# SCH_pie-day-pcb.net
KiCad netlist of a schematic drawn in EasyEDA
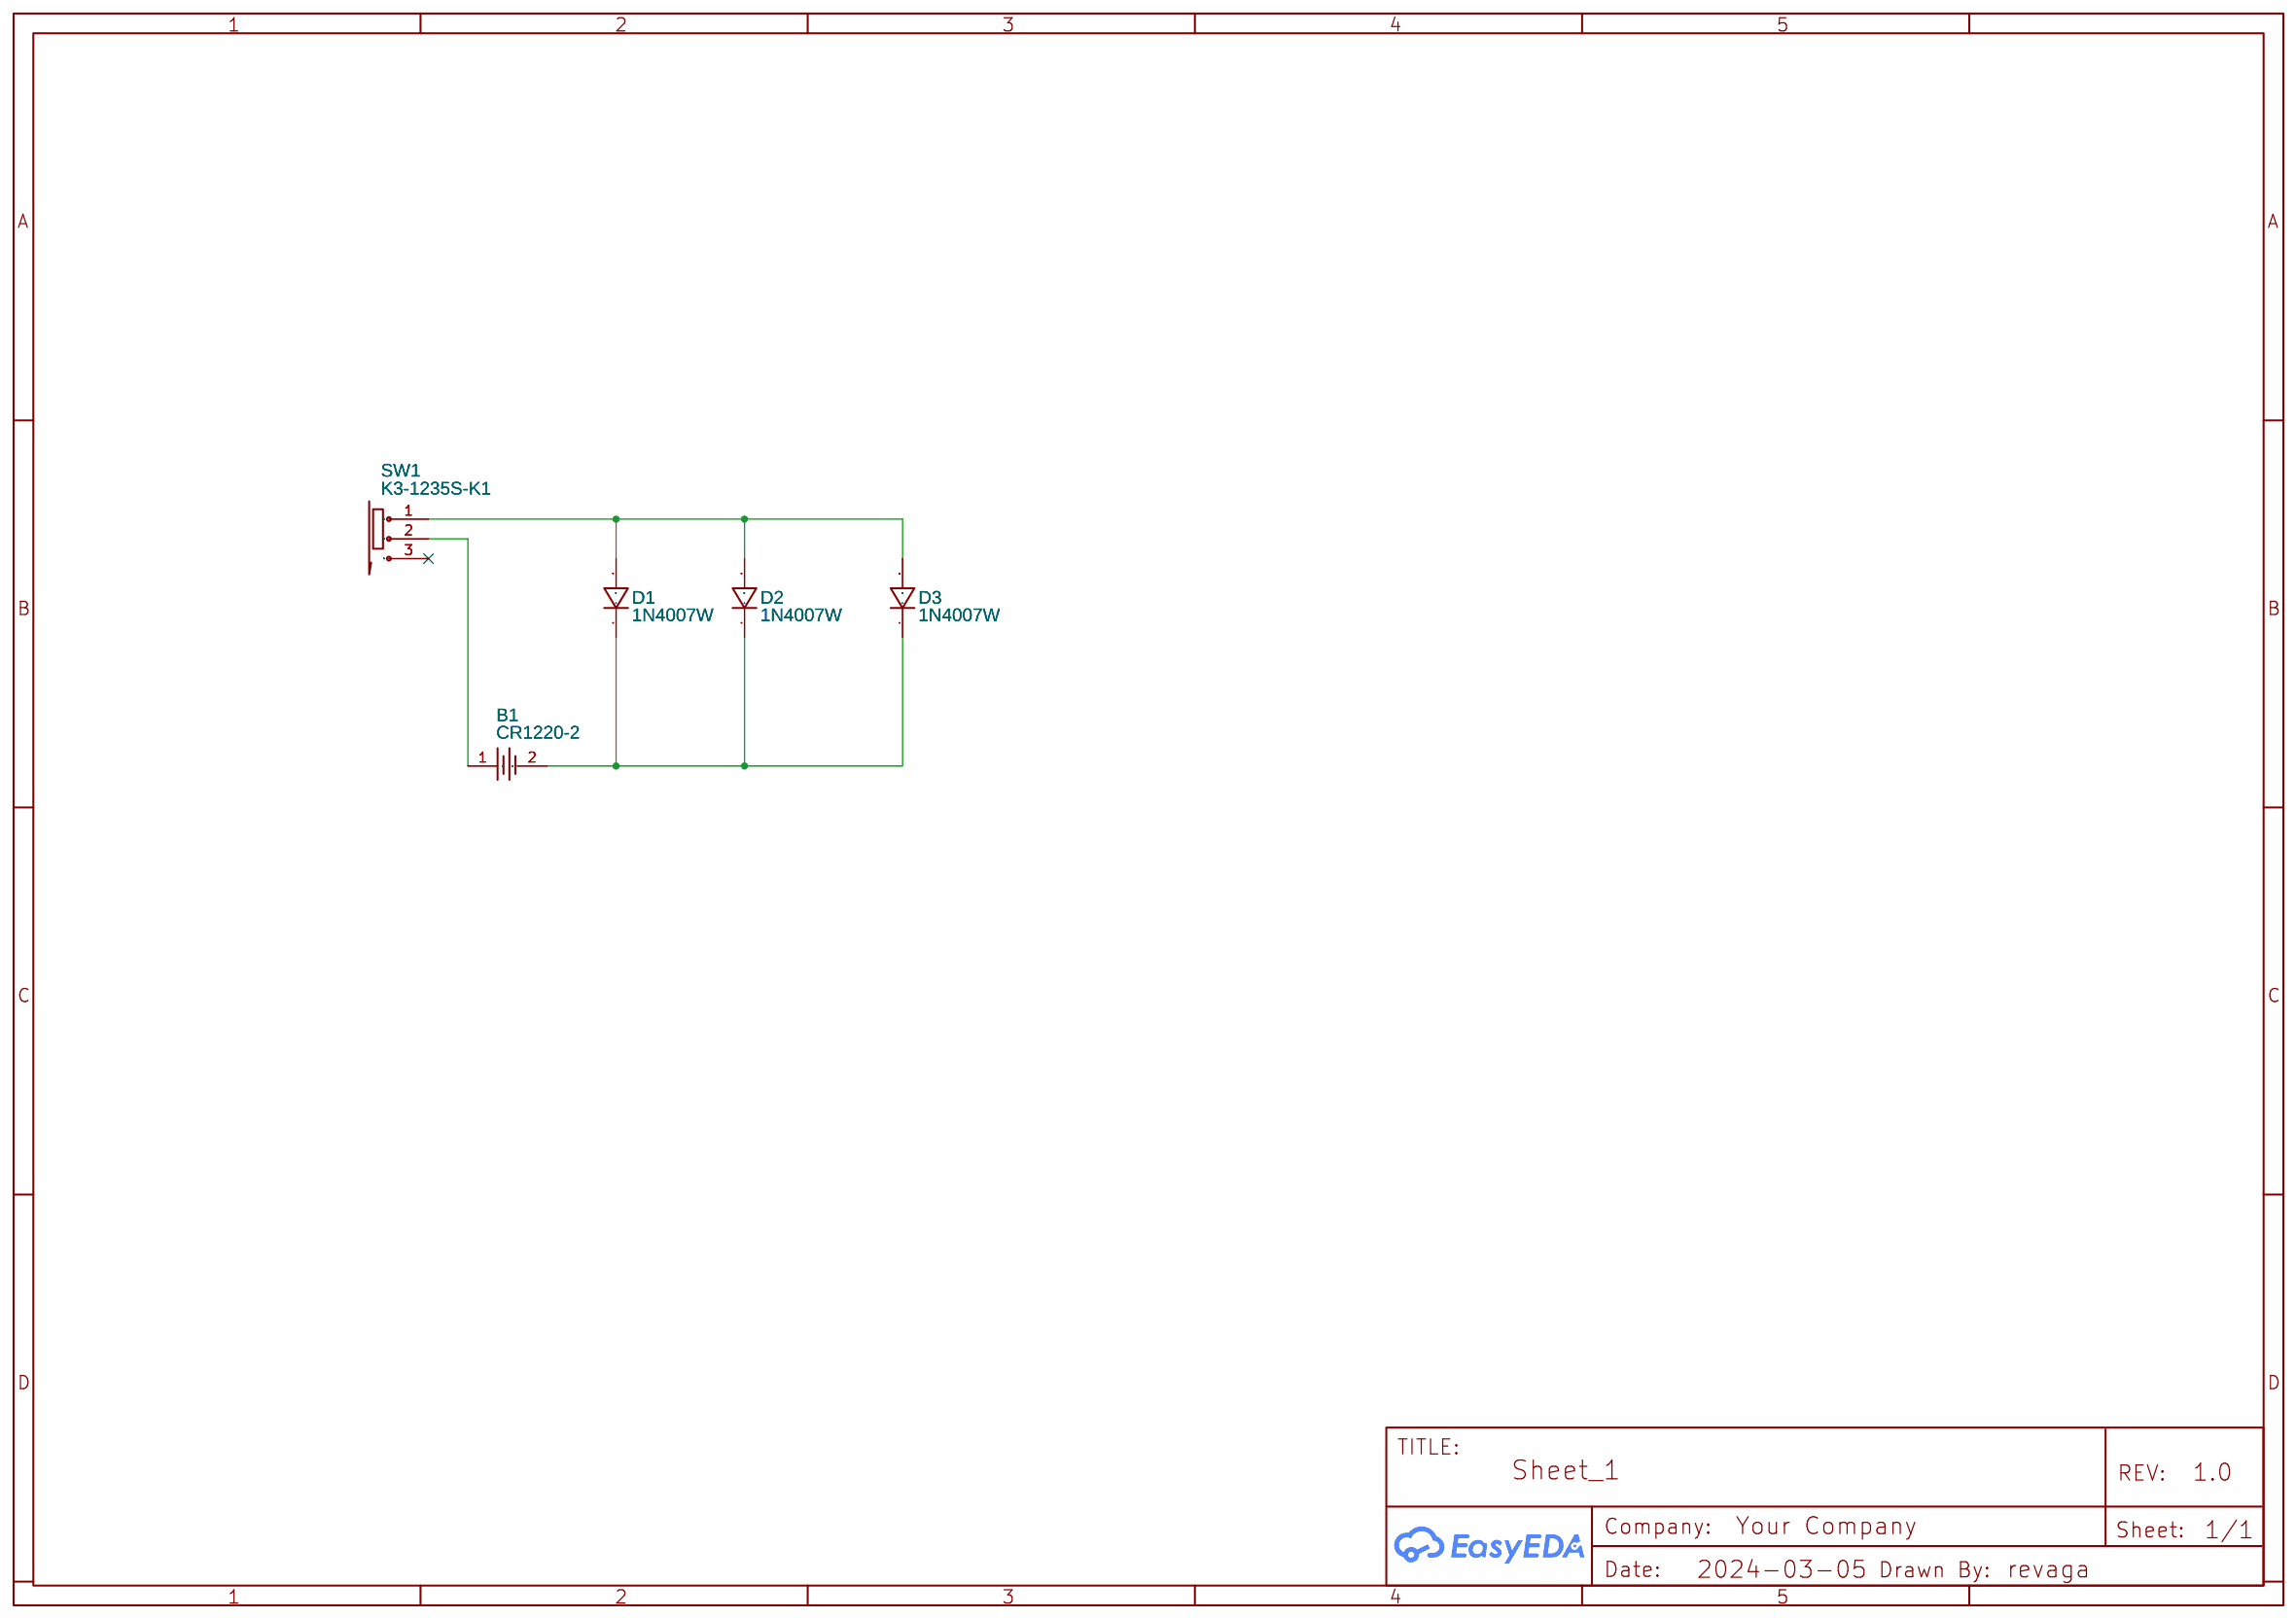
[diagram p0: schematic sheet]

(export (version "E")
  (design (tool "Eeschema 10.0.6"))
  (components
    (comp (ref "B1")
      (value "CR1220-2")
      (fields (field (name "Manufacturer") "Q&J"))
      (libsource (lib "") (part "CR1220-2"))
    )
    (comp (ref "D1")
      (value "1N4007W")
      (fields (field (name "Manufacturer") "BLUE ROCKET"))
      (libsource (lib "") (part "1N4007W"))
    )
    (comp (ref "D2")
      (value "1N4007W")
      (fields (field (name "Manufacturer") "BLUE ROCKET"))
      (libsource (lib "") (part "1N4007W"))
    )
    (comp (ref "D3")
      (value "1N4007W")
      (fields (field (name "Manufacturer") "BLUE ROCKET"))
      (libsource (lib "") (part "1N4007W"))
    )
    (comp (ref "SW1")
      (value "K3-1235S-K1")
      (fields (field (name "Manufacturer") "韩国韩荣"))
      (libsource (lib "") (part "K3-1235S-K1"))
    )
  )
  (nets
    (net (code "1") (name "Net-(B1-Pad1)") (class "Default")
      (node (ref "B1") (pin "1") (pinfunction "1_1") (pintype "input"))
      (node (ref "SW1") (pin "2") (pinfunction "2_2") (pintype "unspecified"))
    )
    (net (code "2") (name "Net-(B1-Pad2)") (class "Default")
      (node (ref "B1") (pin "2") (pinfunction "2_2") (pintype "input"))
      (node (ref "D1") (pin "1") (pinfunction "1_1") (pintype "unspecified"))
      (node (ref "D2") (pin "1") (pinfunction "1_1") (pintype "unspecified"))
      (node (ref "D3") (pin "1") (pinfunction "1_1") (pintype "unspecified"))
    )
    (net (code "3") (name "Net-(D1-Pad2)") (class "Default")
      (node (ref "D1") (pin "2") (pinfunction "2_2") (pintype "unspecified"))
      (node (ref "D2") (pin "2") (pinfunction "2_2") (pintype "unspecified"))
      (node (ref "D3") (pin "2") (pinfunction "2_2") (pintype "unspecified"))
      (node (ref "SW1") (pin "1") (pinfunction "1_1") (pintype "unspecified"))
    )
    (net (code "4") (name "unconnected-(SW1-Pad3)") (class "Default")
      (node (ref "SW1") (pin "3") (pinfunction "3_3") (pintype "unspecified+no_connect"))
    )
  )
)
